# LM25118.net
KiCad netlist of a schematic drawn in Altium Designer
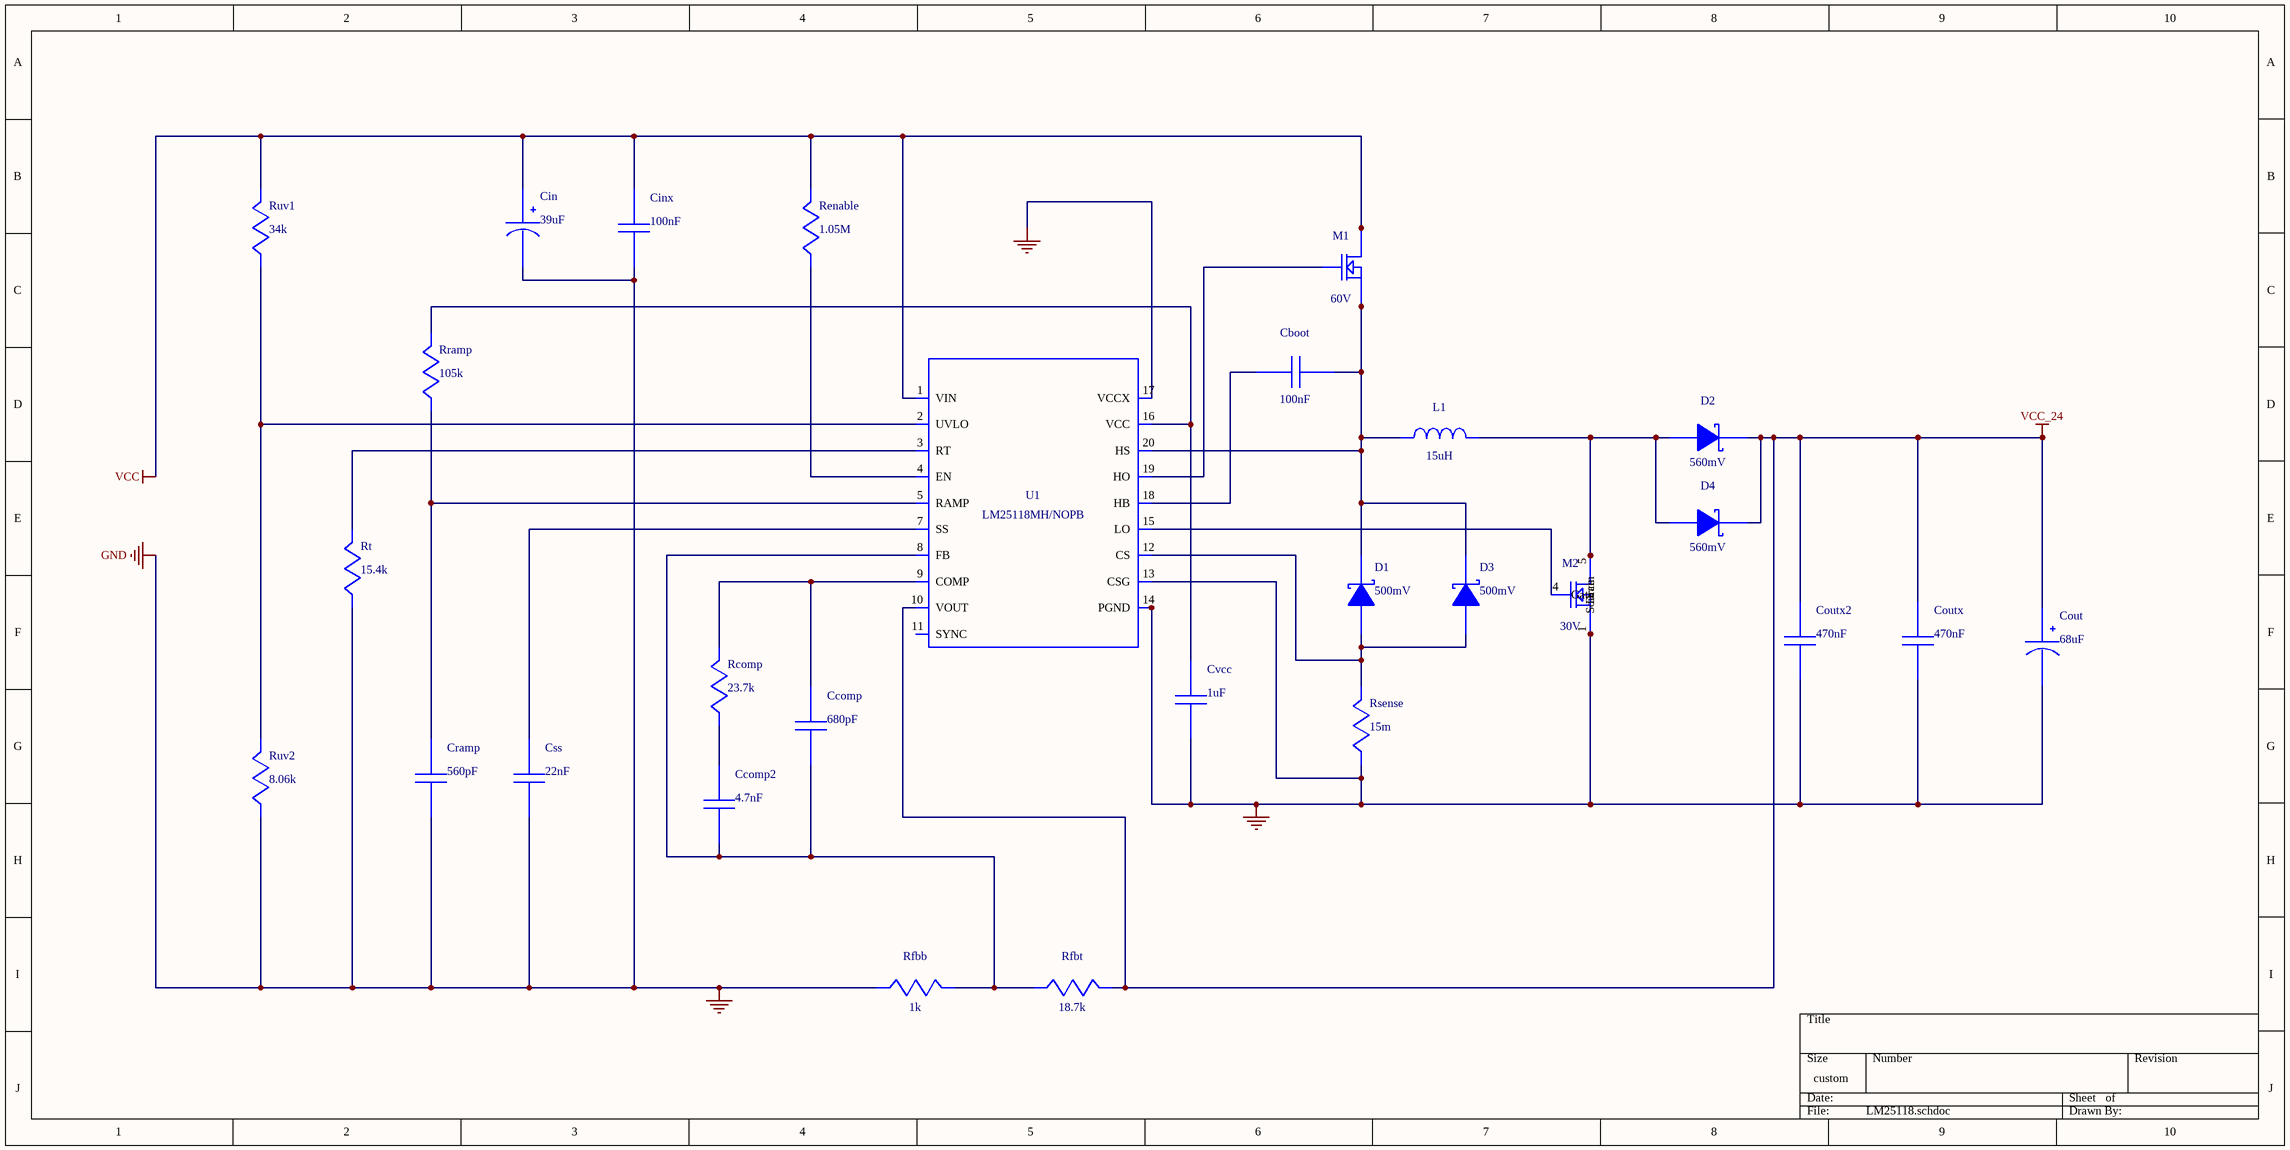
[diagram p0: LM25118.schdoc]

(export (version "E")
  (design (tool "Eeschema 10.0.6"))
  (components
    (comp (ref "Cboot")
      (value "100nF")
      (description "08053C104JAZ2A")
      (libsource (lib "TI WEBENCH") (part "Cboot"))
    )
    (comp (ref "Ccomp")
      (value "680pF")
      (description "CGA2B2C0G1H681J0")
      (fields (field (name "MANUFACTURER PART NUMBER") "CGA2B2C0G1H681J050BA"))
      (libsource (lib "TI WEBENCH") (part "Ccomp"))
    )
    (comp (ref "Ccomp2")
      (value "4.7nF")
      (description "CGA4C2C0G1H472J0")
      (fields (field (name "MANUFACTURER PART NUMBER") "CGA4C2C0G1H472J060AA"))
      (libsource (lib "TI WEBENCH") (part "Ccomp2"))
    )
    (comp (ref "Cin") (value "39uF") (description "50SVPF39M") (libsource (lib "TI WEBENCH") (part "Cin")))
    (comp (ref "Cinx")
      (value "100nF")
      (description "C1005X7R1H104K05")
      (fields (field (name "MANUFACTURER PART NUMBER") "C1005X7R1H104K050BB"))
      (libsource (lib "TI WEBENCH") (part "Cinx"))
    )
    (comp (ref "Cout") (value "68uF") (description "50SVPF68M") (libsource (lib "TI WEBENCH") (part "Cout")))
    (comp (ref "Coutx")
      (value "470nF")
      (description "C1608X7R1H474K08")
      (fields (field (name "MANUFACTURER PART NUMBER") "C1608X7R1H474K080AC"))
      (libsource (lib "TI WEBENCH") (part "Coutx"))
    )
    (comp (ref "Coutx2")
      (value "470nF")
      (description "C1608X7R1H474K08")
      (fields (field (name "MANUFACTURER PART NUMBER") "C1608X7R1H474K080AC"))
      (libsource (lib "TI WEBENCH") (part "Coutx2"))
    )
    (comp (ref "Cramp")
      (value "560pF")
      (description "GRM1555C1H561JA0")
      (fields (field (name "MANUFACTURER PART NUMBER") "GRM1555C1H561JA01J"))
      (libsource (lib "TI WEBENCH") (part "Cramp"))
    )
    (comp (ref "Css")
      (value "22nF")
      (description "CGA4J2C0G1H223J1")
      (fields (field (name "MANUFACTURER PART NUMBER") "CGA4J2C0G1H223J125AA"))
      (libsource (lib "TI WEBENCH") (part "Css"))
    )
    (comp (ref "Cvcc")
      (value "1uF")
      (description "C1608X5R1H105K08")
      (fields (field (name "MANUFACTURER PART NUMBER") "C1608X5R1H105K080AB"))
      (libsource (lib "TI WEBENCH") (part "Cvcc"))
    )
    (comp (ref "D1") (value "500mV") (description "B340A-13-F") (libsource (lib "TI WEBENCH") (part "D1")))
    (comp (ref "D2") (value "560mV") (description "PDS760-13") (libsource (lib "TI WEBENCH") (part "D2")))
    (comp (ref "D3") (value "500mV") (description "B340A-13-F") (libsource (lib "TI WEBENCH") (part "D3")))
    (comp (ref "D4") (value "560mV") (description "PDS760-13") (libsource (lib "TI WEBENCH") (part "D4")))
    (comp (ref "L1") (value "15uH") (description "XAL1010-153MEB") (libsource (lib "TI WEBENCH") (part "L1")))
    (comp (ref "M1") (value "60V") (description "BSZ100N06LS3 G") (libsource (lib "TI WEBENCH") (part "M1")))
    (comp (ref "M2") (value "30V") (description "CSD17308Q3") (libsource (lib "TI WEBENCH") (part "M2")))
    (comp (ref "Rcomp")
      (value "23.7k")
      (description "RC0201FR-0723K7L")
      (libsource (lib "TI WEBENCH") (part "Rcomp"))
    )
    (comp (ref "Renable")
      (value "1.05M")
      (description "CRCW04021M05FKED")
      (libsource (lib "TI WEBENCH") (part "Renable"))
    )
    (comp (ref "Rfbb")
      (value "1k")
      (description "ERJ-6ENF1001V")
      (libsource (lib "TI WEBENCH") (part "Rfbb"))
    )
    (comp (ref "Rfbt")
      (value "18.7k")
      (description "RC0201FR-0718K7L")
      (libsource (lib "TI WEBENCH") (part "Rfbt"))
    )
    (comp (ref "Rramp")
      (value "105k")
      (description "RC0201FR-07105KL")
      (libsource (lib "TI WEBENCH") (part "Rramp"))
    )
    (comp (ref "Rsense")
      (value "15m")
      (description "PRL1632-R015-F-T")
      (fields (field (name "MANUFACTURER PART NUMBER") "PRL1632-R015-F-T1"))
      (libsource (lib "TI WEBENCH") (part "Rsense"))
    )
    (comp (ref "Rt")
      (value "15.4k")
      (description "RC0201FR-0715K4L")
      (libsource (lib "TI WEBENCH") (part "Rt"))
    )
    (comp (ref "Ruv1")
      (value "34k")
      (description "CRCW040234K0FKED")
      (libsource (lib "TI WEBENCH") (part "Ruv1"))
    )
    (comp (ref "Ruv2")
      (value "8.06k")
      (description "CRCW04028K06FKED")
      (libsource (lib "TI WEBENCH") (part "Ruv2"))
    )
    (comp (ref "U1")
      (value "LM25118MH/NOPB")
      (fields (field (name "PACKAGEREFERENCE") "LM25118MH/NOPB"))
      (libsource (lib "TI WEBENCH") (part "U1"))
    )
  )
  (nets
    (net (code "1") (name "0") (class "Default")
      (node (ref "Cin") (pin "2") (pinfunction "-_2") (pintype "passive"))
      (node (ref "Cinx") (pin "2") (pinfunction "2_2") (pintype "passive"))
      (node (ref "Cout") (pin "2") (pinfunction "-_2") (pintype "passive"))
      (node (ref "Coutx") (pin "2") (pinfunction "2_2") (pintype "passive"))
      (node (ref "Coutx2") (pin "2") (pinfunction "2_2") (pintype "passive"))
      (node (ref "Cramp") (pin "2") (pinfunction "2_2") (pintype "passive"))
      (node (ref "Css") (pin "2") (pinfunction "2_2") (pintype "passive"))
      (node (ref "Cvcc") (pin "2") (pinfunction "2_2") (pintype "passive"))
      (node (ref "M2") (pin "1") (pinfunction "Source_1") (pintype "passive"))
      (node (ref "M2") (pin "2") (pinfunction "Source_2") (pintype "passive"))
      (node (ref "M2") (pin "3") (pinfunction "Source_3") (pintype "passive"))
      (node (ref "Rfbb") (pin "2") (pinfunction "2_2") (pintype "passive"))
      (node (ref "Rsense") (pin "2") (pinfunction "2_2") (pintype "passive"))
      (node (ref "Rt") (pin "2") (pinfunction "2_2") (pintype "passive"))
      (node (ref "Ruv2") (pin "2") (pinfunction "2_2") (pintype "passive"))
      (node (ref "U1") (pin "13") (pinfunction "CSG_13") (pintype "passive"))
      (node (ref "U1") (pin "14") (pinfunction "PGND_14") (pintype "passive"))
      (node (ref "U1") (pin "17") (pinfunction "VCCX_17") (pintype "passive"))
      (node (ref "U1") (pin "21") (pinfunction "EXP-PAD_21") (pintype "passive"))
      (node (ref "U1") (pin "6") (pinfunction "AGND_6") (pintype "passive"))
    )
    (net (code "2") (name "Net-(Ccomp2-Pad1)") (class "Default")
      (node (ref "Ccomp2") (pin "1") (pinfunction "1_1") (pintype "passive"))
      (node (ref "Rcomp") (pin "2") (pinfunction "2_2") (pintype "passive"))
    )
    (net (code "3") (name "Net-(D1-A)") (class "Default")
      (node (ref "D1") (pin "2") (pinfunction "A_2") (pintype "passive"))
      (node (ref "D3") (pin "2") (pinfunction "A_2") (pintype "passive"))
      (node (ref "Rsense") (pin "1") (pinfunction "1_1") (pintype "passive"))
      (node (ref "U1") (pin "12") (pinfunction "CS_12") (pintype "passive"))
    )
    (net (code "4") (name "Net-(D1-K)") (class "Default")
      (node (ref "Cboot") (pin "1") (pinfunction "1_1") (pintype "passive"))
      (node (ref "D1") (pin "1") (pinfunction "K_1") (pintype "passive"))
      (node (ref "D3") (pin "1") (pinfunction "K_1") (pintype "passive"))
      (node (ref "L1") (pin "2") (pinfunction "2_2") (pintype "passive"))
      (node (ref "M1") (pin "1") (pinfunction "Source_1") (pintype "passive"))
      (node (ref "M1") (pin "2") (pinfunction "Source_2") (pintype "passive"))
      (node (ref "M1") (pin "3") (pinfunction "Source_3") (pintype "passive"))
      (node (ref "U1") (pin "20") (pinfunction "HS_20") (pintype "passive"))
    )
    (net (code "5") (name "Net-(D2-A)") (class "Default")
      (node (ref "D2") (pin "1") (pinfunction "A_1") (pintype "passive"))
      (node (ref "D4") (pin "1") (pinfunction "A_1") (pintype "passive"))
      (node (ref "L1") (pin "1") (pinfunction "1_1") (pintype "passive"))
      (node (ref "M2") (pin "5") (pinfunction "Drain_5") (pintype "passive"))
      (node (ref "M2") (pin "6") (pinfunction "Drain_6") (pintype "passive"))
      (node (ref "M2") (pin "7") (pinfunction "Drain_7") (pintype "passive"))
      (node (ref "M2") (pin "8") (pinfunction "Drain_8") (pintype "passive"))
      (node (ref "M2") (pin "9") (pinfunction "Drain_9") (pintype "passive"))
    )
    (net (code "6") (name "Net-(M1-Gate)") (class "Default")
      (node (ref "M1") (pin "4") (pinfunction "Gate_4") (pintype "passive"))
      (node (ref "U1") (pin "19") (pinfunction "HO_19") (pintype "passive"))
    )
    (net (code "7") (name "Net-(M2-Gate)") (class "Default")
      (node (ref "M2") (pin "4") (pinfunction "Gate_4") (pintype "passive"))
      (node (ref "U1") (pin "15") (pinfunction "LO_15") (pintype "passive"))
    )
    (net (code "8") (name "Net-(U1-COMP)") (class "Default")
      (node (ref "Ccomp") (pin "1") (pinfunction "1_1") (pintype "passive"))
      (node (ref "Rcomp") (pin "1") (pinfunction "1_1") (pintype "passive"))
      (node (ref "U1") (pin "9") (pinfunction "COMP_9") (pintype "passive"))
    )
    (net (code "9") (name "Net-(U1-EN)") (class "Default")
      (node (ref "Renable") (pin "2") (pinfunction "2_2") (pintype "passive"))
      (node (ref "U1") (pin "4") (pinfunction "EN_4") (pintype "passive"))
    )
    (net (code "10") (name "Net-(U1-FB)") (class "Default")
      (node (ref "Ccomp") (pin "2") (pinfunction "2_2") (pintype "passive"))
      (node (ref "Ccomp2") (pin "2") (pinfunction "2_2") (pintype "passive"))
      (node (ref "Rfbb") (pin "1") (pinfunction "1_1") (pintype "passive"))
      (node (ref "Rfbt") (pin "2") (pinfunction "2_2") (pintype "passive"))
      (node (ref "U1") (pin "8") (pinfunction "FB_8") (pintype "passive"))
    )
    (net (code "11") (name "Net-(U1-HB)") (class "Default")
      (node (ref "Cboot") (pin "2") (pinfunction "2_2") (pintype "passive"))
      (node (ref "U1") (pin "18") (pinfunction "HB_18") (pintype "passive"))
    )
    (net (code "12") (name "Net-(U1-RAMP)") (class "Default")
      (node (ref "Cramp") (pin "1") (pinfunction "1_1") (pintype "passive"))
      (node (ref "Rramp") (pin "2") (pinfunction "2_2") (pintype "passive"))
      (node (ref "U1") (pin "5") (pinfunction "RAMP_5") (pintype "passive"))
    )
    (net (code "13") (name "Net-(U1-RT)") (class "Default")
      (node (ref "Rt") (pin "1") (pinfunction "1_1") (pintype "passive"))
      (node (ref "U1") (pin "3") (pinfunction "RT_3") (pintype "passive"))
    )
    (net (code "14") (name "Net-(U1-SS)") (class "Default")
      (node (ref "Css") (pin "1") (pinfunction "1_1") (pintype "passive"))
      (node (ref "U1") (pin "7") (pinfunction "SS_7") (pintype "passive"))
    )
    (net (code "15") (name "Net-(U1-UVLO)") (class "Default")
      (node (ref "Ruv1") (pin "2") (pinfunction "2_2") (pintype "passive"))
      (node (ref "Ruv2") (pin "1") (pinfunction "1_1") (pintype "passive"))
      (node (ref "U1") (pin "2") (pinfunction "UVLO_2") (pintype "passive"))
    )
    (net (code "16") (name "Net-(U1-VCC)") (class "Default")
      (node (ref "Cvcc") (pin "1") (pinfunction "1_1") (pintype "passive"))
      (node (ref "Rramp") (pin "1") (pinfunction "1_1") (pintype "passive"))
      (node (ref "U1") (pin "16") (pinfunction "VCC_16") (pintype "passive"))
    )
    (net (code "17") (name "VCC") (class "Default")
      (node (ref "Cin") (pin "1") (pinfunction "+_1") (pintype "passive"))
      (node (ref "Cinx") (pin "1") (pinfunction "1_1") (pintype "passive"))
      (node (ref "M1") (pin "5") (pinfunction "Drain_5") (pintype "passive"))
      (node (ref "M1") (pin "6") (pinfunction "Drain_6") (pintype "passive"))
      (node (ref "M1") (pin "7") (pinfunction "Drain_7") (pintype "passive"))
      (node (ref "M1") (pin "8") (pinfunction "Drain_8") (pintype "passive"))
      (node (ref "M1") (pin "9") (pinfunction "Drain_9") (pintype "passive"))
      (node (ref "Renable") (pin "1") (pinfunction "1_1") (pintype "passive"))
      (node (ref "Ruv1") (pin "1") (pinfunction "1_1") (pintype "passive"))
      (node (ref "U1") (pin "1") (pinfunction "VIN_1") (pintype "passive"))
    )
    (net (code "18") (name "VCC_24") (class "Default")
      (node (ref "Cout") (pin "1") (pinfunction "+_1") (pintype "passive"))
      (node (ref "Coutx") (pin "1") (pinfunction "1_1") (pintype "passive"))
      (node (ref "Coutx2") (pin "1") (pinfunction "1_1") (pintype "passive"))
      (node (ref "D2") (pin "2") (pinfunction "K_2") (pintype "passive"))
      (node (ref "D4") (pin "2") (pinfunction "K_2") (pintype "passive"))
      (node (ref "Rfbt") (pin "1") (pinfunction "1_1") (pintype "passive"))
      (node (ref "U1") (pin "10") (pinfunction "VOUT_10") (pintype "passive"))
    )
    (net (code "19") (name "unconnected-(U1-SYNC-Pad11)") (class "Default")
      (node (ref "U1") (pin "11") (pinfunction "SYNC_11") (pintype "passive"))
    )
  )
)
